# FqMeterBF_noali.net
KiCad netlist of a schematic drawn in EAGLE
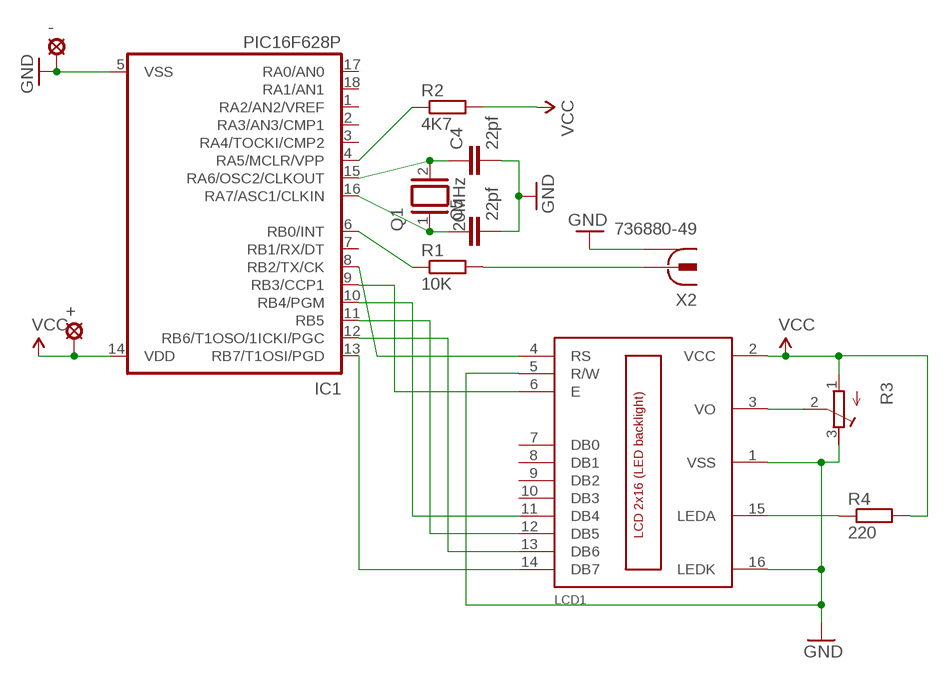
[diagram p0: schematic, sheet 1]

(export (version "E")
  (design (tool "Eeschema 10.0.6"))
  (components
    (comp (ref "+")
      (value "LSP10")
      (footprint "eagle-import:LSP10")
      (libsource (lib "eagle-import") (part "LSP10"))
    )
    (comp (ref "-")
      (value "LSP10")
      (footprint "eagle-import:LSP10")
      (libsource (lib "eagle-import") (part "LSP10"))
    )
    (comp (ref "C4")
      (value "22pf")
      (footprint "eagle-import:C025-024X044")
      (libsource (lib "eagle-import") (part "C-EU025-024X044"))
    )
    (comp (ref "C5")
      (value "22pf")
      (footprint "eagle-import:C025-024X044")
      (libsource (lib "eagle-import") (part "C-EU025-024X044"))
    )
    (comp (ref "IC1")
      (value "PIC16F628P")
      (footprint "eagle-import:DIL18")
      (fields (field (name "MF") "MICROCHIP") (field (name "MPN") "PIC16F628-20/P"))
      (libsource (lib "eagle-import") (part "PIC16F628P"))
    )
    (comp (ref "LCD1")
      (value "LCD_2X16")
      (footprint "eagle-import:HY-1602F")
      (libsource (lib "eagle-import") (part "LCD_2X16"))
    )
    (comp (ref "Q1")
      (value "20MHz")
      (footprint "eagle-import:QS")
      (libsource (lib "eagle-import") (part "XTAL/S"))
    )
    (comp (ref "R1")
      (value "10K")
      (footprint "eagle-import:0207_12")
      (libsource (lib "eagle-import") (part "R-EU_0207/12"))
    )
    (comp (ref "R2")
      (value "4K7")
      (footprint "eagle-import:0207_12")
      (libsource (lib "eagle-import") (part "R-EU_0207/12"))
    )
    (comp (ref "R3")
      (value "R-TRIMM3339P")
      (footprint "eagle-import:RTRIM3339P")
      (libsource (lib "eagle-import") (part "R-TRIMM3339P"))
    )
    (comp (ref "R4")
      (value "220")
      (footprint "eagle-import:0207_12")
      (libsource (lib "eagle-import") (part "R-EU_0207/12"))
    )
    (comp (ref "X2")
      (value "736880-49")
      (footprint "eagle-import:736880-49")
      (libsource (lib "eagle-import") (part "736880-49"))
    )
  )
  (nets
    (net (code "1") (name "GND") (class "Default")
      (node (ref "-") (pin "MP") (pinfunction "MP_MP") (pintype "passive"))
      (node (ref "C4") (pin "2") (pinfunction "2_2") (pintype "passive"))
      (node (ref "C5") (pin "2") (pinfunction "2_2") (pintype "passive"))
      (node (ref "IC1") (pin "5") (pinfunction "VSS_5") (pintype "power_in"))
      (node (ref "LCD1") (pin "1") (pinfunction "VSS_1") (pintype "power_in"))
      (node (ref "LCD1") (pin "16") (pinfunction "LEDK_16") (pintype "passive"))
      (node (ref "LCD1") (pin "5") (pinfunction "R/W_5") (pintype "input"))
      (node (ref "R3") (pin "3") (pinfunction "E_3") (pintype "passive"))
      (node (ref "X2") (pin "1") (pinfunction "1_1") (pintype "passive"))
      (node (ref "X2") (pin "1@1") (pinfunction "1_1@1") (pintype "passive"))
      (node (ref "X2") (pin "1@2") (pinfunction "1_1@2") (pintype "passive"))
    )
    (net (code "2") (name "Net-(IC1-RA5{slash}MCLR{slash}VPP)") (class "Default")
      (node (ref "IC1") (pin "4") (pinfunction "RA5/MCLR/VPP_4") (pintype "input"))
      (node (ref "R2") (pin "1") (pinfunction "1_1") (pintype "passive"))
    )
    (net (code "3") (name "Net-(IC1-RA6{slash}OSC2{slash}CLKOUT)") (class "Default")
      (node (ref "C4") (pin "1") (pinfunction "1_1") (pintype "passive"))
      (node (ref "IC1") (pin "15") (pinfunction "RA6/OSC2/CLKOUT_15") (pintype "bidirectional"))
      (node (ref "Q1") (pin "2") (pinfunction "2_2") (pintype "passive"))
    )
    (net (code "4") (name "Net-(IC1-RA7{slash}ASC1{slash}CLKIN)") (class "Default")
      (node (ref "C5") (pin "1") (pinfunction "1_1") (pintype "passive"))
      (node (ref "IC1") (pin "16") (pinfunction "RA7/ASC1/CLKIN_16") (pintype "bidirectional"))
      (node (ref "Q1") (pin "1") (pinfunction "1_1") (pintype "passive"))
    )
    (net (code "5") (name "Net-(IC1-RB0{slash}INT)") (class "Default")
      (node (ref "IC1") (pin "6") (pinfunction "RB0/INT_6") (pintype "bidirectional"))
      (node (ref "R1") (pin "1") (pinfunction "1_1") (pintype "passive"))
    )
    (net (code "6") (name "Net-(IC1-RB2{slash}TX{slash}CK)") (class "Default")
      (node (ref "IC1") (pin "8") (pinfunction "RB2/TX/CK_8") (pintype "bidirectional"))
      (node (ref "LCD1") (pin "4") (pinfunction "RS_4") (pintype "input"))
    )
    (net (code "7") (name "Net-(IC1-RB3{slash}CCP1)") (class "Default")
      (node (ref "IC1") (pin "9") (pinfunction "RB3/CCP1_9") (pintype "bidirectional"))
      (node (ref "LCD1") (pin "6") (pinfunction "E_6") (pintype "input"))
    )
    (net (code "8") (name "Net-(IC1-RB4{slash}PGM)") (class "Default")
      (node (ref "IC1") (pin "10") (pinfunction "RB4/PGM_10") (pintype "bidirectional"))
      (node (ref "LCD1") (pin "11") (pinfunction "DB4_11") (pintype "bidirectional"))
    )
    (net (code "9") (name "Net-(IC1-RB5)") (class "Default")
      (node (ref "IC1") (pin "11") (pinfunction "RB5_11") (pintype "bidirectional"))
      (node (ref "LCD1") (pin "12") (pinfunction "DB5_12") (pintype "bidirectional"))
    )
    (net (code "10") (name "Net-(IC1-RB6{slash}T1OSO{slash}1ICKI{slash}PGC)") (class "Default")
      (node (ref "IC1") (pin "12") (pinfunction "RB6/T1OSO/1ICKI/PGC_12") (pintype "bidirectional"))
      (node (ref "LCD1") (pin "13") (pinfunction "DB6_13") (pintype "bidirectional"))
    )
    (net (code "11") (name "Net-(IC1-RB7{slash}T1OSI{slash}PGD)") (class "Default")
      (node (ref "IC1") (pin "13") (pinfunction "RB7/T1OSI/PGD_13") (pintype "bidirectional"))
      (node (ref "LCD1") (pin "14") (pinfunction "DB7_14") (pintype "bidirectional"))
    )
    (net (code "12") (name "Net-(LCD1-LEDA)") (class "Default")
      (node (ref "LCD1") (pin "15") (pinfunction "LEDA_15") (pintype "passive"))
      (node (ref "R4") (pin "1") (pinfunction "1_1") (pintype "passive"))
    )
    (net (code "13") (name "Net-(LCD1-VO)") (class "Default")
      (node (ref "LCD1") (pin "3") (pinfunction "VO_3") (pintype "input"))
      (node (ref "R3") (pin "2") (pinfunction "S_2") (pintype "passive"))
    )
    (net (code "14") (name "Net-(R1-Pad2)") (class "Default")
      (node (ref "R1") (pin "2") (pinfunction "2_2") (pintype "passive"))
      (node (ref "X2") (pin "2") (pinfunction "2_2") (pintype "passive"))
    )
    (net (code "15") (name "VCC") (class "Default")
      (node (ref "+") (pin "MP") (pinfunction "MP_MP") (pintype "passive"))
      (node (ref "IC1") (pin "14") (pinfunction "VDD_14") (pintype "power_in"))
      (node (ref "LCD1") (pin "2") (pinfunction "VCC_2") (pintype "power_in"))
      (node (ref "R2") (pin "2") (pinfunction "2_2") (pintype "passive"))
      (node (ref "R3") (pin "1") (pinfunction "A_1") (pintype "passive"))
      (node (ref "R4") (pin "2") (pinfunction "2_2") (pintype "passive"))
    )
    (net (code "16") (name "unconnected-(IC1-RA0{slash}AN0-Pad17)") (class "Default")
      (node (ref "IC1") (pin "17") (pinfunction "RA0/AN0_17") (pintype "bidirectional"))
    )
    (net (code "17") (name "unconnected-(IC1-RA1{slash}AN1-Pad18)") (class "Default")
      (node (ref "IC1") (pin "18") (pinfunction "RA1/AN1_18") (pintype "bidirectional"))
    )
    (net (code "18") (name "unconnected-(IC1-RA2{slash}AN2{slash}VREF-Pad1)") (class "Default")
      (node (ref "IC1") (pin "1") (pinfunction "RA2/AN2/VREF_1") (pintype "bidirectional"))
    )
    (net (code "19") (name "unconnected-(IC1-RA3{slash}AN3{slash}CMP1-Pad2)") (class "Default")
      (node (ref "IC1") (pin "2") (pinfunction "RA3/AN3/CMP1_2") (pintype "bidirectional"))
    )
    (net (code "20") (name "unconnected-(IC1-RA4{slash}TOCKI{slash}CMP2-Pad3)") (class "Default")
      (node (ref "IC1") (pin "3") (pinfunction "RA4/TOCKI/CMP2_3") (pintype "bidirectional"))
    )
    (net (code "21") (name "unconnected-(IC1-RB1{slash}RX{slash}DT-Pad7)") (class "Default")
      (node (ref "IC1") (pin "7") (pinfunction "RB1/RX/DT_7") (pintype "bidirectional"))
    )
    (net (code "22") (name "unconnected-(LCD1-DB0-Pad7)") (class "Default")
      (node (ref "LCD1") (pin "7") (pinfunction "DB0_7") (pintype "bidirectional"))
    )
    (net (code "23") (name "unconnected-(LCD1-DB1-Pad8)") (class "Default")
      (node (ref "LCD1") (pin "8") (pinfunction "DB1_8") (pintype "bidirectional"))
    )
    (net (code "24") (name "unconnected-(LCD1-DB2-Pad9)") (class "Default")
      (node (ref "LCD1") (pin "9") (pinfunction "DB2_9") (pintype "bidirectional"))
    )
    (net (code "25") (name "unconnected-(LCD1-DB3-Pad10)") (class "Default")
      (node (ref "LCD1") (pin "10") (pinfunction "DB3_10") (pintype "bidirectional"))
    )
  )
)
